# BCI_Controller.net
KiCad netlist of a schematic drawn in EAGLE
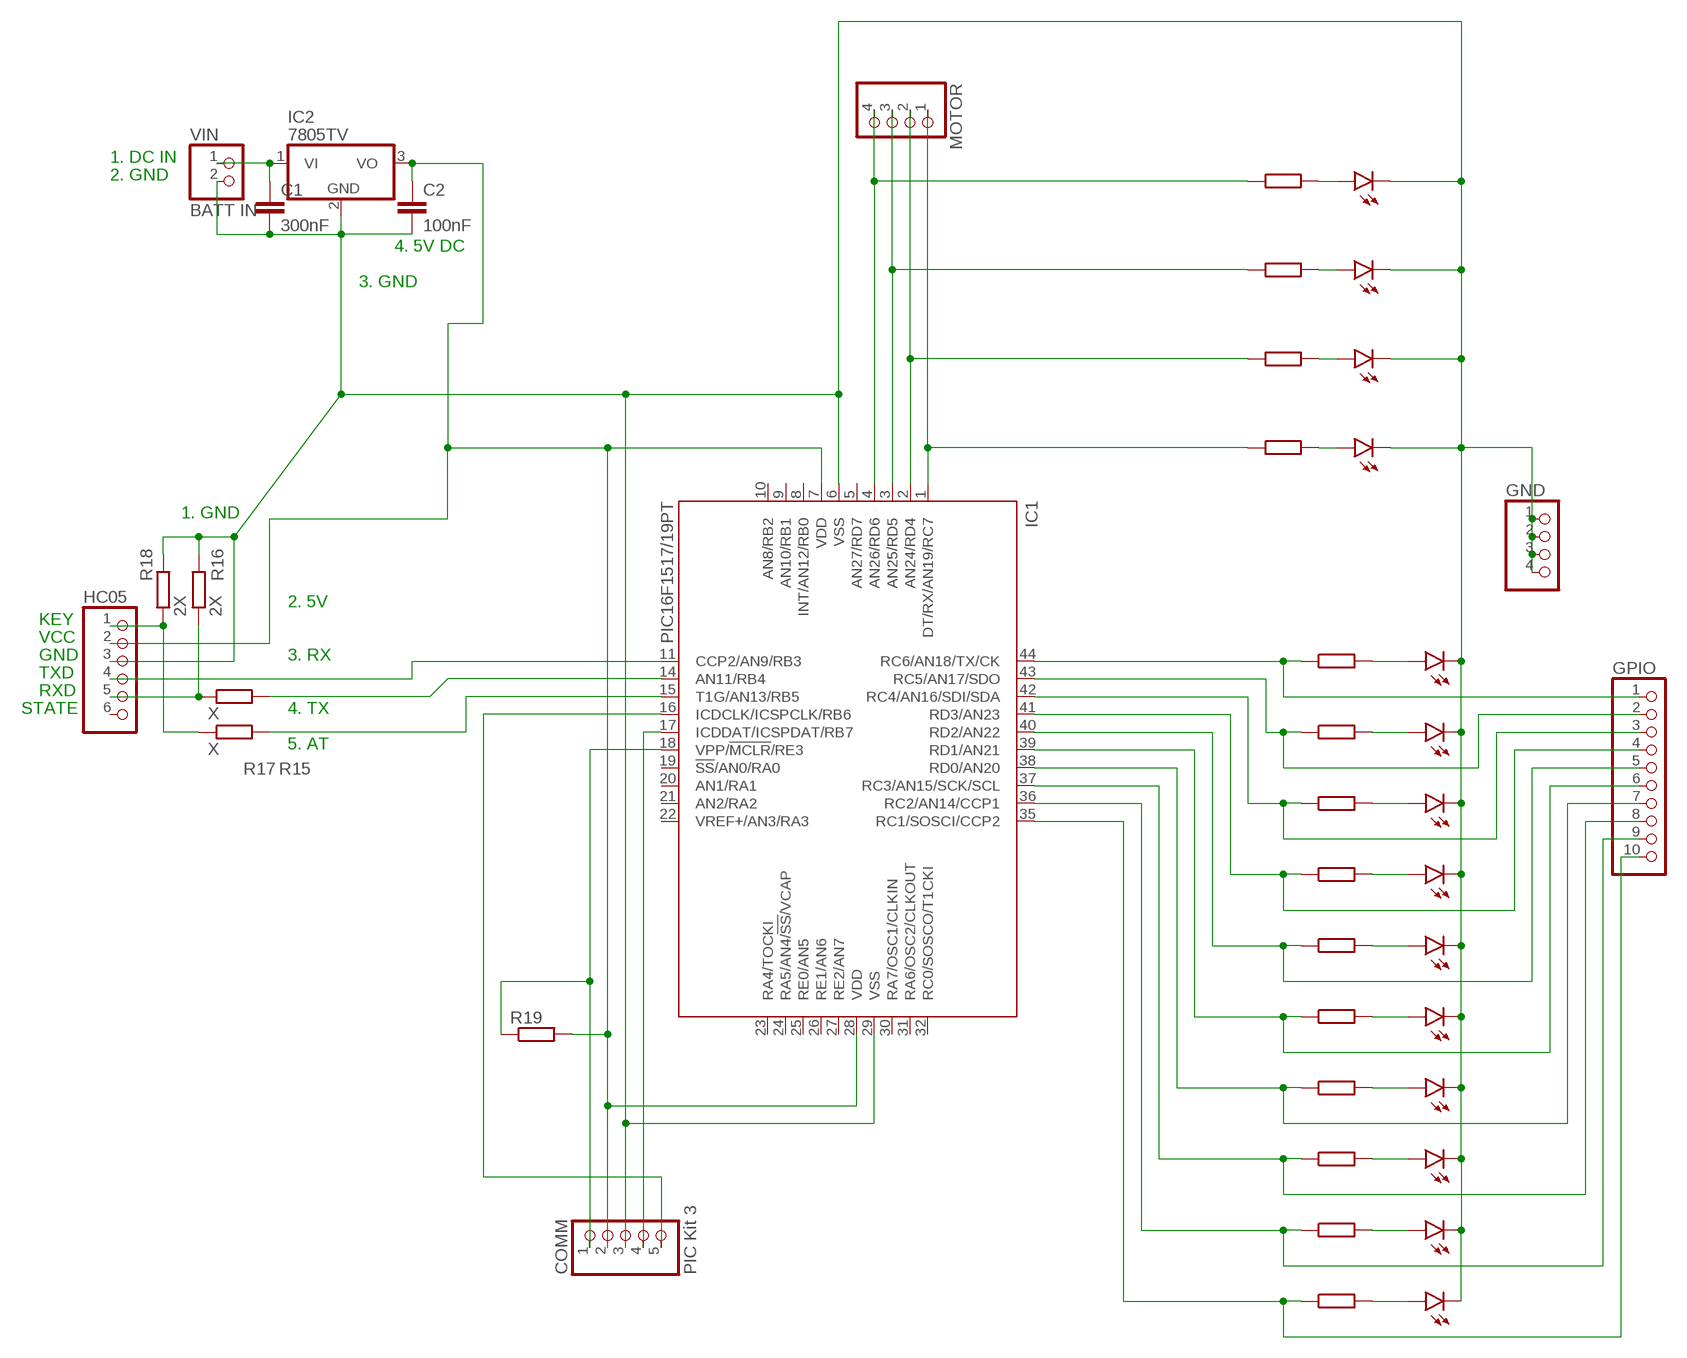
[diagram p0: schematic, sheet 1]

(export (version "E")
  (design (tool "Eeschema 10.0.6"))
  (components
    (comp (ref "C1")
      (value "300nF")
      (footprint "eagle-import:C1206")
      (libsource (lib "eagle-import") (part "C-EUC1206"))
    )
    (comp (ref "C2")
      (value "100nF")
      (footprint "eagle-import:C1206")
      (libsource (lib "eagle-import") (part "C-EUC1206"))
    )
    (comp (ref "COMM")
      (value "PIC Kit 3")
      (footprint "eagle-import:1X05")
      (libsource (lib "eagle-import") (part "PINHD-1X5"))
    )
    (comp (ref "GND")
      (value "PINHD-1X4")
      (footprint "eagle-import:1X04")
      (libsource (lib "eagle-import") (part "PINHD-1X4"))
    )
    (comp (ref "GPIO")
      (value "PINHD-1X10")
      (footprint "eagle-import:1X10")
      (libsource (lib "eagle-import") (part "PINHD-1X10"))
    )
    (comp (ref "HC05")
      (value "PINHD-1X6")
      (footprint "eagle-import:1X06")
      (libsource (lib "eagle-import") (part "PINHD-1X6"))
    )
    (comp (ref "IC1")
      (value "PIC16F1517/19PT")
      (footprint "eagle-import:TQFP44")
      (libsource (lib "eagle-import") (part "PIC16F1517/19PT"))
    )
    (comp (ref "IC2")
      (value "7805TV")
      (footprint "eagle-import:TO220V")
      (libsource (lib "eagle-import") (part "78TV05"))
    )
    (comp (ref "LED1")
      (value "LEDSMT1206")
      (footprint "eagle-import:1206")
      (libsource (lib "eagle-import") (part "LEDSMT1206"))
    )
    (comp (ref "LED2")
      (value "LEDSMT1206")
      (footprint "eagle-import:1206")
      (libsource (lib "eagle-import") (part "LEDSMT1206"))
    )
    (comp (ref "LED3")
      (value "LEDSMT1206")
      (footprint "eagle-import:1206")
      (libsource (lib "eagle-import") (part "LEDSMT1206"))
    )
    (comp (ref "LED4")
      (value "LEDSMT1206")
      (footprint "eagle-import:1206")
      (libsource (lib "eagle-import") (part "LEDSMT1206"))
    )
    (comp (ref "LED5")
      (value "LEDSMT1206")
      (footprint "eagle-import:1206")
      (libsource (lib "eagle-import") (part "LEDSMT1206"))
    )
    (comp (ref "LED6")
      (value "LEDSMT1206")
      (footprint "eagle-import:1206")
      (libsource (lib "eagle-import") (part "LEDSMT1206"))
    )
    (comp (ref "LED7")
      (value "LEDSMT1206")
      (footprint "eagle-import:1206")
      (libsource (lib "eagle-import") (part "LEDSMT1206"))
    )
    (comp (ref "LED8")
      (value "LEDSMT1206")
      (footprint "eagle-import:1206")
      (libsource (lib "eagle-import") (part "LEDSMT1206"))
    )
    (comp (ref "LED9")
      (value "LEDSMT1206")
      (footprint "eagle-import:1206")
      (libsource (lib "eagle-import") (part "LEDSMT1206"))
    )
    (comp (ref "LED10")
      (value "LEDSMT1206")
      (footprint "eagle-import:1206")
      (libsource (lib "eagle-import") (part "LEDSMT1206"))
    )
    (comp (ref "LED11")
      (value "LEDSMT1206")
      (footprint "eagle-import:1206")
      (libsource (lib "eagle-import") (part "LEDSMT1206"))
    )
    (comp (ref "LED12")
      (value "LEDSMT1206")
      (footprint "eagle-import:1206")
      (libsource (lib "eagle-import") (part "LEDSMT1206"))
    )
    (comp (ref "LED13")
      (value "LEDSMT1206")
      (footprint "eagle-import:1206")
      (libsource (lib "eagle-import") (part "LEDSMT1206"))
    )
    (comp (ref "LED14")
      (value "LEDSMT1206")
      (footprint "eagle-import:1206")
      (libsource (lib "eagle-import") (part "LEDSMT1206"))
    )
    (comp (ref "MOTOR")
      (value "PINHD-1X4")
      (footprint "eagle-import:1X04")
      (libsource (lib "eagle-import") (part "PINHD-1X4"))
    )
    (comp (ref "R1")
      (value "R-EU_R1206")
      (footprint "eagle-import:R1206")
      (libsource (lib "eagle-import") (part "R-EU_R1206"))
    )
    (comp (ref "R2")
      (value "R-EU_R1206")
      (footprint "eagle-import:R1206")
      (libsource (lib "eagle-import") (part "R-EU_R1206"))
    )
    (comp (ref "R3")
      (value "R-EU_R1206")
      (footprint "eagle-import:R1206")
      (libsource (lib "eagle-import") (part "R-EU_R1206"))
    )
    (comp (ref "R4")
      (value "R-EU_R1206")
      (footprint "eagle-import:R1206")
      (libsource (lib "eagle-import") (part "R-EU_R1206"))
    )
    (comp (ref "R5")
      (value "R-EU_R1206")
      (footprint "eagle-import:R1206")
      (libsource (lib "eagle-import") (part "R-EU_R1206"))
    )
    (comp (ref "R6")
      (value "R-EU_R1206")
      (footprint "eagle-import:R1206")
      (libsource (lib "eagle-import") (part "R-EU_R1206"))
    )
    (comp (ref "R7")
      (value "R-EU_R1206")
      (footprint "eagle-import:R1206")
      (libsource (lib "eagle-import") (part "R-EU_R1206"))
    )
    (comp (ref "R8")
      (value "R-EU_R1206")
      (footprint "eagle-import:R1206")
      (libsource (lib "eagle-import") (part "R-EU_R1206"))
    )
    (comp (ref "R9")
      (value "R-EU_R1206")
      (footprint "eagle-import:R1206")
      (libsource (lib "eagle-import") (part "R-EU_R1206"))
    )
    (comp (ref "R10")
      (value "R-EU_R1206")
      (footprint "eagle-import:R1206")
      (libsource (lib "eagle-import") (part "R-EU_R1206"))
    )
    (comp (ref "R11")
      (value "R-EU_R1206")
      (footprint "eagle-import:R1206")
      (libsource (lib "eagle-import") (part "R-EU_R1206"))
    )
    (comp (ref "R12")
      (value "R-EU_R1206")
      (footprint "eagle-import:R1206")
      (libsource (lib "eagle-import") (part "R-EU_R1206"))
    )
    (comp (ref "R13")
      (value "R-EU_R1206")
      (footprint "eagle-import:R1206")
      (libsource (lib "eagle-import") (part "R-EU_R1206"))
    )
    (comp (ref "R14")
      (value "R-EU_R1206")
      (footprint "eagle-import:R1206")
      (libsource (lib "eagle-import") (part "R-EU_R1206"))
    )
    (comp (ref "R15")
      (value "X")
      (footprint "eagle-import:M1206")
      (libsource (lib "eagle-import") (part "R-EU_M1206"))
    )
    (comp (ref "R16")
      (value "2X")
      (footprint "eagle-import:M1206")
      (libsource (lib "eagle-import") (part "R-EU_M1206"))
    )
    (comp (ref "R17")
      (value "X")
      (footprint "eagle-import:M1206")
      (libsource (lib "eagle-import") (part "R-EU_M1206"))
    )
    (comp (ref "R18")
      (value "2X")
      (footprint "eagle-import:M1206")
      (libsource (lib "eagle-import") (part "R-EU_M1206"))
    )
    (comp (ref "R19")
      (value "R-EU_M1206")
      (footprint "eagle-import:M1206")
      (libsource (lib "eagle-import") (part "R-EU_M1206"))
    )
    (comp (ref "VIN")
      (value "BATT IN")
      (footprint "eagle-import:1X02")
      (libsource (lib "eagle-import") (part "PINHD-1X2"))
    )
  )
  (nets
    (net (code "1") (name "Net-(HC05-Pad1)") (class "Default")
      (node (ref "HC05") (pin "1") (pinfunction "1_1") (pintype "passive"))
      (node (ref "R17") (pin "1") (pinfunction "1_1") (pintype "passive"))
      (node (ref "R18") (pin "1") (pinfunction "1_1") (pintype "passive"))
    )
    (net (code "2") (name "Net-(HC05-Pad5)") (class "Default")
      (node (ref "HC05") (pin "5") (pinfunction "5_5") (pintype "passive"))
      (node (ref "R15") (pin "1") (pinfunction "1_1") (pintype "passive"))
      (node (ref "R16") (pin "1") (pinfunction "1_1") (pintype "passive"))
    )
    (net (code "3") (name "Net-(IC1-AN11{slash}RB4)") (class "Default")
      (node (ref "IC1") (pin "14") (pinfunction "AN11/RB4_14") (pintype "bidirectional"))
      (node (ref "R15") (pin "2") (pinfunction "2_2") (pintype "passive"))
    )
    (net (code "4") (name "Net-(IC1-AN24{slash}RD4)") (class "Default")
      (node (ref "IC1") (pin "2") (pinfunction "AN24/RD4_2") (pintype "bidirectional"))
      (node (ref "MOTOR") (pin "2") (pinfunction "2_2") (pintype "passive"))
      (node (ref "R13") (pin "1") (pinfunction "1_1") (pintype "passive"))
    )
    (net (code "5") (name "Net-(IC1-AN25{slash}RD5)") (class "Default")
      (node (ref "IC1") (pin "3") (pinfunction "AN25/RD5_3") (pintype "bidirectional"))
      (node (ref "MOTOR") (pin "3") (pinfunction "3_3") (pintype "passive"))
      (node (ref "R12") (pin "1") (pinfunction "1_1") (pintype "passive"))
    )
    (net (code "6") (name "Net-(IC1-AN26{slash}RD6)") (class "Default")
      (node (ref "IC1") (pin "4") (pinfunction "AN26/RD6_4") (pintype "bidirectional"))
      (node (ref "MOTOR") (pin "4") (pinfunction "4_4") (pintype "passive"))
      (node (ref "R11") (pin "1") (pinfunction "1_1") (pintype "passive"))
    )
    (net (code "7") (name "Net-(IC1-CCP2{slash}AN9{slash}RB3)") (class "Default")
      (node (ref "HC05") (pin "4") (pinfunction "4_4") (pintype "passive"))
      (node (ref "IC1") (pin "11") (pinfunction "CCP2/AN9/RB3_11") (pintype "bidirectional"))
    )
    (net (code "8") (name "Net-(IC1-DT{slash}RX{slash}AN19{slash}RC7)") (class "Default")
      (node (ref "IC1") (pin "1") (pinfunction "DT/RX/AN19/RC7_1") (pintype "bidirectional"))
      (node (ref "MOTOR") (pin "1") (pinfunction "1_1") (pintype "passive"))
      (node (ref "R14") (pin "1") (pinfunction "1_1") (pintype "passive"))
    )
    (net (code "9") (name "Net-(IC1-ICDCLK{slash}ICSPCLK{slash}RB6)") (class "Default")
      (node (ref "COMM") (pin "5") (pinfunction "5_5") (pintype "passive"))
      (node (ref "IC1") (pin "16") (pinfunction "ICDCLK/ICSPCLK/RB6_16") (pintype "bidirectional"))
    )
    (net (code "10") (name "Net-(IC1-ICDDAT{slash}ICSPDAT{slash}RB7)") (class "Default")
      (node (ref "COMM") (pin "4") (pinfunction "4_4") (pintype "passive"))
      (node (ref "IC1") (pin "17") (pinfunction "ICDDAT/ICSPDAT/RB7_17") (pintype "bidirectional"))
    )
    (net (code "11") (name "Net-(IC1-RC1{slash}SOSCI{slash}CCP2)") (class "Default")
      (node (ref "GPIO") (pin "10") (pinfunction "10_10") (pintype "passive"))
      (node (ref "IC1") (pin "35") (pinfunction "RC1/SOSCI/CCP2_35") (pintype "bidirectional"))
      (node (ref "R10") (pin "1") (pinfunction "1_1") (pintype "passive"))
    )
    (net (code "12") (name "Net-(IC1-RC2{slash}AN14{slash}CCP1)") (class "Default")
      (node (ref "GPIO") (pin "9") (pinfunction "9_9") (pintype "passive"))
      (node (ref "IC1") (pin "36") (pinfunction "RC2/AN14/CCP1_36") (pintype "bidirectional"))
      (node (ref "R9") (pin "1") (pinfunction "1_1") (pintype "passive"))
    )
    (net (code "13") (name "Net-(IC1-RC3{slash}AN15{slash}SCK{slash}SCL)") (class "Default")
      (node (ref "GPIO") (pin "8") (pinfunction "8_8") (pintype "passive"))
      (node (ref "IC1") (pin "37") (pinfunction "RC3/AN15/SCK/SCL_37") (pintype "bidirectional"))
      (node (ref "R8") (pin "1") (pinfunction "1_1") (pintype "passive"))
    )
    (net (code "14") (name "Net-(IC1-RC4{slash}AN16{slash}SDI{slash}SDA)") (class "Default")
      (node (ref "GPIO") (pin "3") (pinfunction "3_3") (pintype "passive"))
      (node (ref "IC1") (pin "42") (pinfunction "RC4/AN16/SDI/SDA_42") (pintype "bidirectional"))
      (node (ref "R3") (pin "1") (pinfunction "1_1") (pintype "passive"))
    )
    (net (code "15") (name "Net-(IC1-RC5{slash}AN17{slash}SDO)") (class "Default")
      (node (ref "GPIO") (pin "2") (pinfunction "2_2") (pintype "passive"))
      (node (ref "IC1") (pin "43") (pinfunction "RC5/AN17/SDO_43") (pintype "bidirectional"))
      (node (ref "R2") (pin "1") (pinfunction "1_1") (pintype "passive"))
    )
    (net (code "16") (name "Net-(IC1-RC6{slash}AN18{slash}TX{slash}CK)") (class "Default")
      (node (ref "GPIO") (pin "1") (pinfunction "1_1") (pintype "passive"))
      (node (ref "IC1") (pin "44") (pinfunction "RC6/AN18/TX/CK_44") (pintype "bidirectional"))
      (node (ref "R1") (pin "1") (pinfunction "1_1") (pintype "passive"))
    )
    (net (code "17") (name "Net-(IC1-RD0{slash}AN20)") (class "Default")
      (node (ref "GPIO") (pin "7") (pinfunction "7_7") (pintype "passive"))
      (node (ref "IC1") (pin "38") (pinfunction "RD0/AN20_38") (pintype "bidirectional"))
      (node (ref "R7") (pin "1") (pinfunction "1_1") (pintype "passive"))
    )
    (net (code "18") (name "Net-(IC1-RD1{slash}AN21)") (class "Default")
      (node (ref "GPIO") (pin "6") (pinfunction "6_6") (pintype "passive"))
      (node (ref "IC1") (pin "39") (pinfunction "RD1/AN21_39") (pintype "bidirectional"))
      (node (ref "R6") (pin "1") (pinfunction "1_1") (pintype "passive"))
    )
    (net (code "19") (name "Net-(IC1-RD2{slash}AN22)") (class "Default")
      (node (ref "GPIO") (pin "5") (pinfunction "5_5") (pintype "passive"))
      (node (ref "IC1") (pin "40") (pinfunction "RD2/AN22_40") (pintype "bidirectional"))
      (node (ref "R5") (pin "1") (pinfunction "1_1") (pintype "passive"))
    )
    (net (code "20") (name "Net-(IC1-RD3{slash}AN23)") (class "Default")
      (node (ref "GPIO") (pin "4") (pinfunction "4_4") (pintype "passive"))
      (node (ref "IC1") (pin "41") (pinfunction "RD3/AN23_41") (pintype "bidirectional"))
      (node (ref "R4") (pin "1") (pinfunction "1_1") (pintype "passive"))
    )
    (net (code "21") (name "Net-(IC1-T1G{slash}AN13{slash}RB5)") (class "Default")
      (node (ref "IC1") (pin "15") (pinfunction "T1G/AN13/RB5_15") (pintype "bidirectional"))
      (node (ref "R17") (pin "2") (pinfunction "2_2") (pintype "passive"))
    )
    (net (code "22") (name "Net-(IC1-VPP{slash}~{MCLR}{slash}RE3)") (class "Default")
      (node (ref "COMM") (pin "1") (pinfunction "1_1") (pintype "passive"))
      (node (ref "IC1") (pin "18") (pinfunction "VPP/~{MCLR}/RE3_18") (pintype "input"))
      (node (ref "R19") (pin "1") (pinfunction "1_1") (pintype "passive"))
    )
    (net (code "23") (name "Net-(IC2-GND)") (class "Default")
      (node (ref "C1") (pin "2") (pinfunction "2_2") (pintype "passive"))
      (node (ref "C2") (pin "2") (pinfunction "2_2") (pintype "passive"))
      (node (ref "COMM") (pin "3") (pinfunction "3_3") (pintype "passive"))
      (node (ref "GND") (pin "1") (pinfunction "1_1") (pintype "passive"))
      (node (ref "GND") (pin "2") (pinfunction "2_2") (pintype "passive"))
      (node (ref "GND") (pin "3") (pinfunction "3_3") (pintype "passive"))
      (node (ref "GND") (pin "4") (pinfunction "4_4") (pintype "passive"))
      (node (ref "HC05") (pin "3") (pinfunction "3_3") (pintype "passive"))
      (node (ref "IC1") (pin "29") (pinfunction "VSS_29") (pintype "power_in"))
      (node (ref "IC1") (pin "6") (pinfunction "VSS_6") (pintype "power_in"))
      (node (ref "IC2") (pin "2") (pinfunction "GND_2") (pintype "passive"))
      (node (ref "LED1") (pin "C") (pinfunction "C_C") (pintype "passive"))
      (node (ref "LED10") (pin "C") (pinfunction "C_C") (pintype "passive"))
      (node (ref "LED11") (pin "C") (pinfunction "C_C") (pintype "passive"))
      (node (ref "LED12") (pin "C") (pinfunction "C_C") (pintype "passive"))
      (node (ref "LED13") (pin "C") (pinfunction "C_C") (pintype "passive"))
      (node (ref "LED14") (pin "C") (pinfunction "C_C") (pintype "passive"))
      (node (ref "LED2") (pin "C") (pinfunction "C_C") (pintype "passive"))
      (node (ref "LED3") (pin "C") (pinfunction "C_C") (pintype "passive"))
      (node (ref "LED4") (pin "C") (pinfunction "C_C") (pintype "passive"))
      (node (ref "LED5") (pin "C") (pinfunction "C_C") (pintype "passive"))
      (node (ref "LED6") (pin "C") (pinfunction "C_C") (pintype "passive"))
      (node (ref "LED7") (pin "C") (pinfunction "C_C") (pintype "passive"))
      (node (ref "LED8") (pin "C") (pinfunction "C_C") (pintype "passive"))
      (node (ref "LED9") (pin "C") (pinfunction "C_C") (pintype "passive"))
      (node (ref "R16") (pin "2") (pinfunction "2_2") (pintype "passive"))
      (node (ref "R18") (pin "2") (pinfunction "2_2") (pintype "passive"))
      (node (ref "VIN") (pin "2") (pinfunction "2_2") (pintype "passive"))
    )
    (net (code "24") (name "Net-(IC2-VI)") (class "Default")
      (node (ref "C1") (pin "1") (pinfunction "1_1") (pintype "passive"))
      (node (ref "IC2") (pin "1") (pinfunction "VI_1") (pintype "input"))
      (node (ref "VIN") (pin "1") (pinfunction "1_1") (pintype "passive"))
    )
    (net (code "25") (name "Net-(IC2-VO)") (class "Default")
      (node (ref "C2") (pin "1") (pinfunction "1_1") (pintype "passive"))
      (node (ref "COMM") (pin "2") (pinfunction "2_2") (pintype "passive"))
      (node (ref "HC05") (pin "2") (pinfunction "2_2") (pintype "passive"))
      (node (ref "IC1") (pin "28") (pinfunction "VDD_28") (pintype "power_in"))
      (node (ref "IC1") (pin "7") (pinfunction "VDD_7") (pintype "power_in"))
      (node (ref "IC2") (pin "3") (pinfunction "VO_3") (pintype "passive"))
      (node (ref "R19") (pin "2") (pinfunction "2_2") (pintype "passive"))
    )
    (net (code "26") (name "Net-(LED1-PadA)") (class "Default")
      (node (ref "LED1") (pin "A") (pinfunction "A_A") (pintype "passive"))
      (node (ref "R1") (pin "2") (pinfunction "2_2") (pintype "passive"))
    )
    (net (code "27") (name "Net-(LED2-PadA)") (class "Default")
      (node (ref "LED2") (pin "A") (pinfunction "A_A") (pintype "passive"))
      (node (ref "R2") (pin "2") (pinfunction "2_2") (pintype "passive"))
    )
    (net (code "28") (name "Net-(LED3-PadA)") (class "Default")
      (node (ref "LED3") (pin "A") (pinfunction "A_A") (pintype "passive"))
      (node (ref "R3") (pin "2") (pinfunction "2_2") (pintype "passive"))
    )
    (net (code "29") (name "Net-(LED4-PadA)") (class "Default")
      (node (ref "LED4") (pin "A") (pinfunction "A_A") (pintype "passive"))
      (node (ref "R4") (pin "2") (pinfunction "2_2") (pintype "passive"))
    )
    (net (code "30") (name "Net-(LED5-PadA)") (class "Default")
      (node (ref "LED5") (pin "A") (pinfunction "A_A") (pintype "passive"))
      (node (ref "R5") (pin "2") (pinfunction "2_2") (pintype "passive"))
    )
    (net (code "31") (name "Net-(LED6-PadA)") (class "Default")
      (node (ref "LED6") (pin "A") (pinfunction "A_A") (pintype "passive"))
      (node (ref "R6") (pin "2") (pinfunction "2_2") (pintype "passive"))
    )
    (net (code "32") (name "Net-(LED7-PadA)") (class "Default")
      (node (ref "LED7") (pin "A") (pinfunction "A_A") (pintype "passive"))
      (node (ref "R7") (pin "2") (pinfunction "2_2") (pintype "passive"))
    )
    (net (code "33") (name "Net-(LED8-PadA)") (class "Default")
      (node (ref "LED8") (pin "A") (pinfunction "A_A") (pintype "passive"))
      (node (ref "R8") (pin "2") (pinfunction "2_2") (pintype "passive"))
    )
    (net (code "34") (name "Net-(LED9-PadA)") (class "Default")
      (node (ref "LED9") (pin "A") (pinfunction "A_A") (pintype "passive"))
      (node (ref "R9") (pin "2") (pinfunction "2_2") (pintype "passive"))
    )
    (net (code "35") (name "Net-(LED10-PadA)") (class "Default")
      (node (ref "LED10") (pin "A") (pinfunction "A_A") (pintype "passive"))
      (node (ref "R10") (pin "2") (pinfunction "2_2") (pintype "passive"))
    )
    (net (code "36") (name "Net-(LED11-PadA)") (class "Default")
      (node (ref "LED11") (pin "A") (pinfunction "A_A") (pintype "passive"))
      (node (ref "R14") (pin "2") (pinfunction "2_2") (pintype "passive"))
    )
    (net (code "37") (name "Net-(LED12-PadA)") (class "Default")
      (node (ref "LED12") (pin "A") (pinfunction "A_A") (pintype "passive"))
      (node (ref "R13") (pin "2") (pinfunction "2_2") (pintype "passive"))
    )
    (net (code "38") (name "Net-(LED13-PadA)") (class "Default")
      (node (ref "LED13") (pin "A") (pinfunction "A_A") (pintype "passive"))
      (node (ref "R12") (pin "2") (pinfunction "2_2") (pintype "passive"))
    )
    (net (code "39") (name "Net-(LED14-PadA)") (class "Default")
      (node (ref "LED14") (pin "A") (pinfunction "A_A") (pintype "passive"))
      (node (ref "R11") (pin "2") (pinfunction "2_2") (pintype "passive"))
    )
    (net (code "40") (name "unconnected-(HC05-Pad6)") (class "Default")
      (node (ref "HC05") (pin "6") (pinfunction "6_6") (pintype "passive"))
    )
    (net (code "41") (name "unconnected-(IC1-AN1{slash}RA1-Pad20)") (class "Default")
      (node (ref "IC1") (pin "20") (pinfunction "AN1/RA1_20") (pintype "bidirectional"))
    )
    (net (code "42") (name "unconnected-(IC1-AN2{slash}RA2-Pad21)") (class "Default")
      (node (ref "IC1") (pin "21") (pinfunction "AN2/RA2_21") (pintype "bidirectional"))
    )
    (net (code "43") (name "unconnected-(IC1-AN8{slash}RB2-Pad10)") (class "Default")
      (node (ref "IC1") (pin "10") (pinfunction "AN8/RB2_10") (pintype "bidirectional"))
    )
    (net (code "44") (name "unconnected-(IC1-AN10{slash}RB1-Pad9)") (class "Default")
      (node (ref "IC1") (pin "9") (pinfunction "AN10/RB1_9") (pintype "bidirectional"))
    )
    (net (code "45") (name "unconnected-(IC1-AN27{slash}RD7-Pad5)") (class "Default")
      (node (ref "IC1") (pin "5") (pinfunction "AN27/RD7_5") (pintype "bidirectional"))
    )
    (net (code "46") (name "unconnected-(IC1-INT{slash}AN12{slash}RB0-Pad8)") (class "Default")
      (node (ref "IC1") (pin "8") (pinfunction "INT/AN12/RB0_8") (pintype "bidirectional"))
    )
    (net (code "47") (name "unconnected-(IC1-RA4{slash}TOCKI-Pad23)") (class "Default")
      (node (ref "IC1") (pin "23") (pinfunction "RA4/TOCKI_23") (pintype "bidirectional"))
    )
    (net (code "48") (name "unconnected-(IC1-RA5{slash}AN4{slash}~{SS}{slash}VCAP-Pad24)") (class "Default")
      (node (ref "IC1") (pin "24") (pinfunction "RA5/AN4/~{SS}/VCAP_24") (pintype "bidirectional"))
    )
    (net (code "49") (name "unconnected-(IC1-RA6{slash}OSC2{slash}CLKOUT-Pad31)") (class "Default")
      (node (ref "IC1") (pin "31") (pinfunction "RA6/OSC2/CLKOUT_31") (pintype "bidirectional"))
    )
    (net (code "50") (name "unconnected-(IC1-RA7{slash}OSC1{slash}CLKIN-Pad30)") (class "Default")
      (node (ref "IC1") (pin "30") (pinfunction "RA7/OSC1/CLKIN_30") (pintype "bidirectional"))
    )
    (net (code "51") (name "unconnected-(IC1-RC0{slash}SOSCO{slash}T1CKI-Pad32)") (class "Default")
      (node (ref "IC1") (pin "32") (pinfunction "RC0/SOSCO/T1CKI_32") (pintype "bidirectional"))
    )
    (net (code "52") (name "unconnected-(IC1-RE0{slash}AN5-Pad25)") (class "Default")
      (node (ref "IC1") (pin "25") (pinfunction "RE0/AN5_25") (pintype "bidirectional"))
    )
    (net (code "53") (name "unconnected-(IC1-RE1{slash}AN6-Pad26)") (class "Default")
      (node (ref "IC1") (pin "26") (pinfunction "RE1/AN6_26") (pintype "bidirectional"))
    )
    (net (code "54") (name "unconnected-(IC1-RE2{slash}AN7-Pad27)") (class "Default")
      (node (ref "IC1") (pin "27") (pinfunction "RE2/AN7_27") (pintype "bidirectional"))
    )
    (net (code "55") (name "unconnected-(IC1-VREF+{slash}AN3{slash}RA3-Pad22)") (class "Default")
      (node (ref "IC1") (pin "22") (pinfunction "VREF+/AN3/RA3_22") (pintype "bidirectional"))
    )
    (net (code "56") (name "unconnected-(IC1-~{SS}{slash}AN0{slash}RA0-Pad19)") (class "Default")
      (node (ref "IC1") (pin "19") (pinfunction "~{SS}/AN0/RA0_19") (pintype "bidirectional"))
    )
  )
)
